# piston_slave.net
KiCad netlist of a schematic drawn in EAGLE
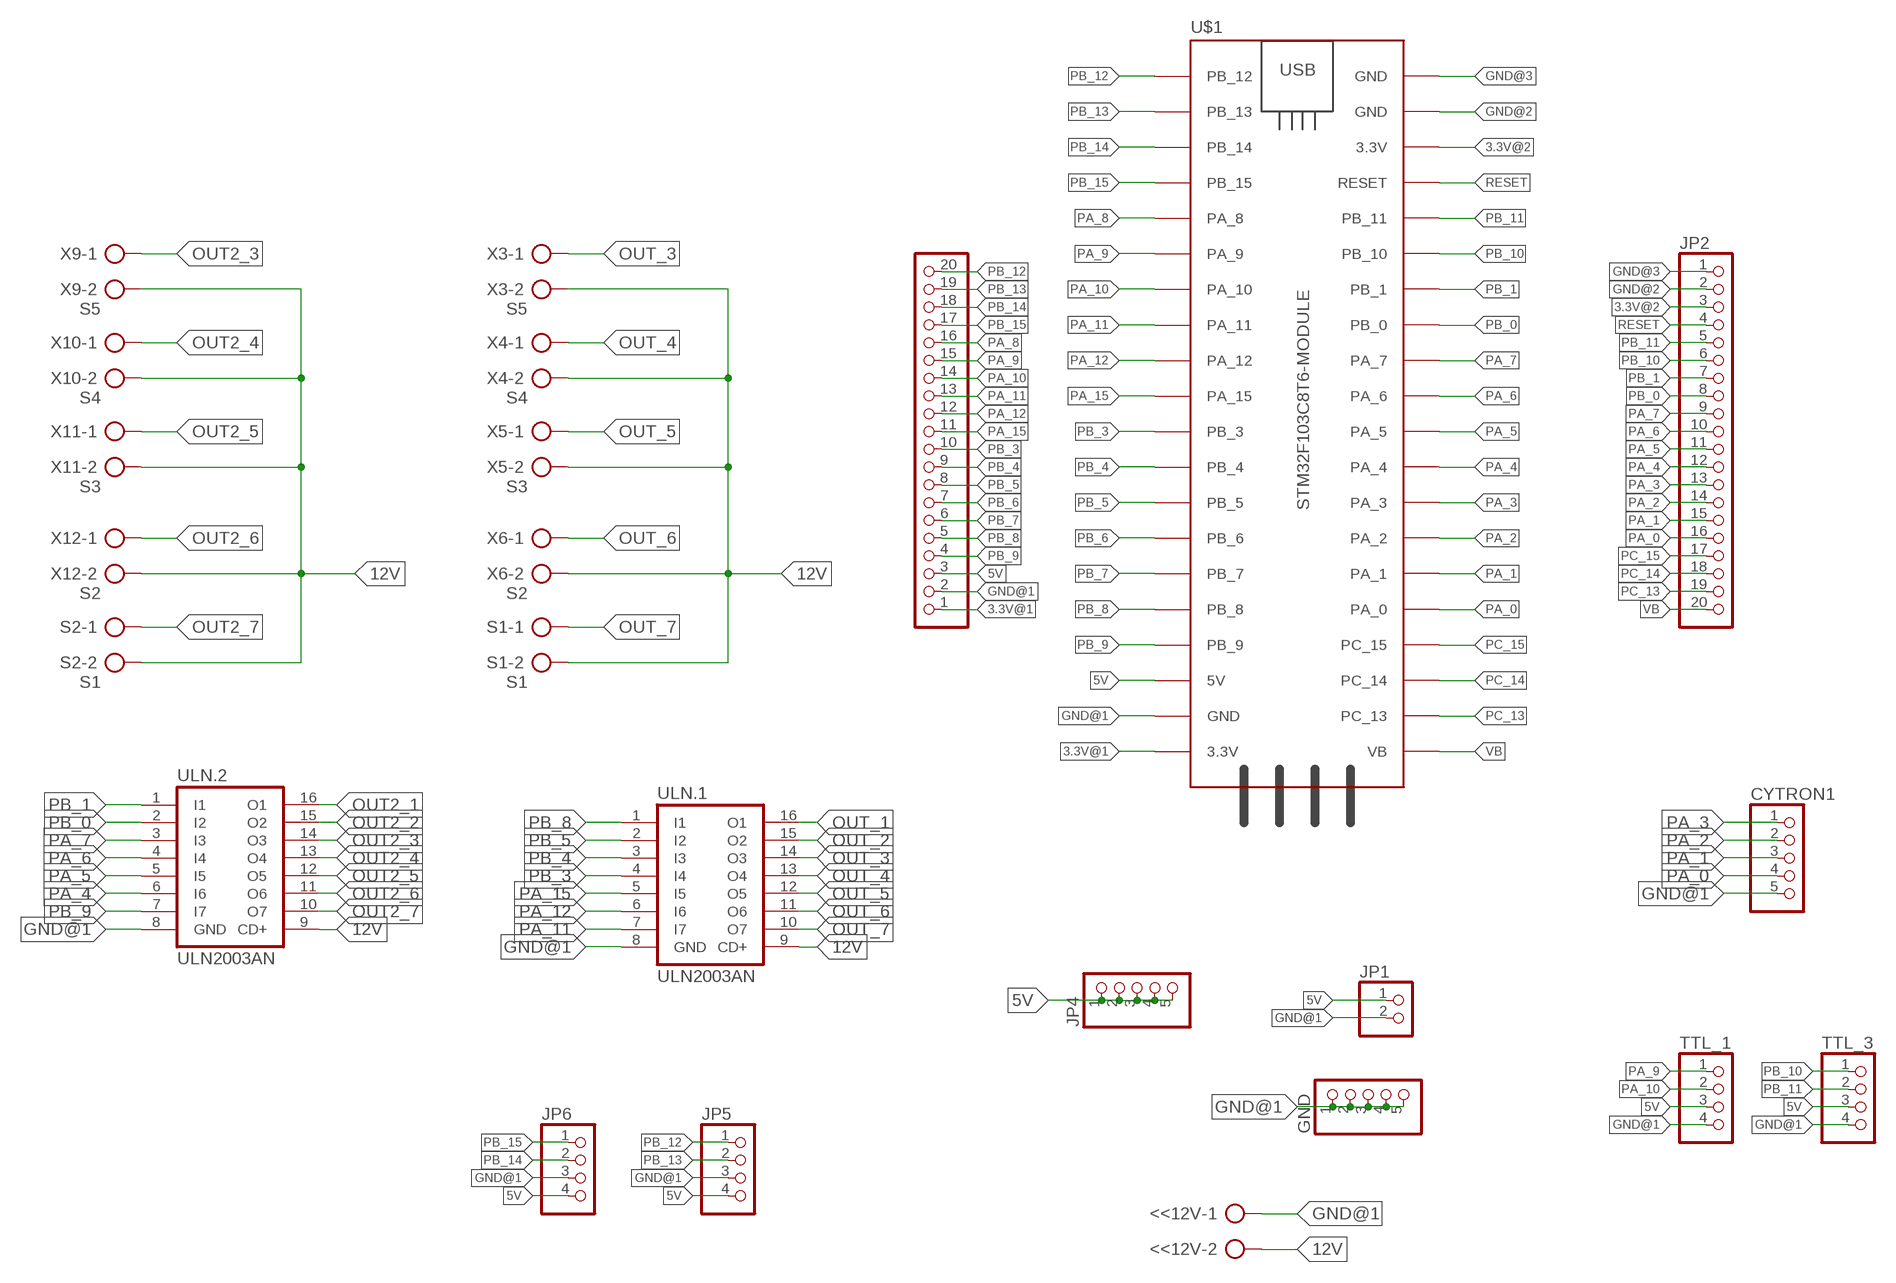
[diagram p0: schematic, sheet 1]

(export (version "E")
  (design (tool "Eeschema 10.0.6"))
  (components
    (comp (ref "<<12V")
      (value "AK300/2")
      (footprint "eagle-import:AK300_2")
      (libsource (lib "eagle-import") (part "AK300/2"))
    )
    (comp (ref "CYTRON1")
      (value "PINHD-5_DATA")
      (footprint "eagle-import:DATA_5")
      (libsource (lib "eagle-import") (part "PINHD-5_DATA"))
    )
    (comp (ref "GND")
      (value "PINHD-1X5")
      (footprint "eagle-import:1X05")
      (libsource (lib "eagle-import") (part "PINHD-1X5"))
    )
    (comp (ref "JP1")
      (value "PINHD-2_DATA")
      (footprint "eagle-import:1X02_DATA")
      (libsource (lib "eagle-import") (part "PINHD-2_DATA"))
    )
    (comp (ref "JP2")
      (value "PINHD-1X20")
      (footprint "eagle-import:1X20")
      (libsource (lib "eagle-import") (part "PINHD-1X20"))
    )
    (comp (ref "JP3")
      (value "PINHD-1X20")
      (footprint "eagle-import:1X20")
      (libsource (lib "eagle-import") (part "PINHD-1X20"))
    )
    (comp (ref "JP4")
      (value "PINHD-1X5")
      (footprint "eagle-import:1X05")
      (libsource (lib "eagle-import") (part "PINHD-1X5"))
    )
    (comp (ref "JP5")
      (value "PINHD-4_DATA")
      (footprint "eagle-import:1X04_DATA")
      (libsource (lib "eagle-import") (part "PINHD-4_DATA"))
    )
    (comp (ref "JP6")
      (value "PINHD-4_DATA")
      (footprint "eagle-import:1X04_DATA")
      (libsource (lib "eagle-import") (part "PINHD-4_DATA"))
    )
    (comp (ref "S1")
      (value "S1")
      (footprint "eagle-import:AK300_2")
      (libsource (lib "eagle-import") (part "AK300/2"))
    )
    (comp (ref "S2")
      (value "S1")
      (footprint "eagle-import:AK300_2")
      (libsource (lib "eagle-import") (part "AK300/2"))
    )
    (comp (ref "TTL_1")
      (value "PINHD-4_DATA")
      (footprint "eagle-import:1X04_DATA")
      (libsource (lib "eagle-import") (part "PINHD-4_DATA"))
    )
    (comp (ref "TTL_3")
      (value "PINHD-4_DATA")
      (footprint "eagle-import:1X04_DATA")
      (libsource (lib "eagle-import") (part "PINHD-4_DATA"))
    )
    (comp (ref "U$1")
      (value "STM32F103C8T6-MODULE")
      (footprint "eagle-import:STM32F103C8T6-MODULE")
      (libsource (lib "eagle-import") (part "STM32F103C8T6-MODULE"))
    )
    (comp (ref "ULN.1")
      (value "ULN2003AN")
      (footprint "eagle-import:DIL16")
      (libsource (lib "eagle-import") (part "ULN2003AN"))
    )
    (comp (ref "ULN.2")
      (value "ULN2003AN")
      (footprint "eagle-import:DIL16")
      (libsource (lib "eagle-import") (part "ULN2003AN"))
    )
    (comp (ref "X3")
      (value "S5")
      (footprint "eagle-import:AK300_2")
      (libsource (lib "eagle-import") (part "AK300/2"))
    )
    (comp (ref "X4")
      (value "S4")
      (footprint "eagle-import:AK300_2")
      (libsource (lib "eagle-import") (part "AK300/2"))
    )
    (comp (ref "X5")
      (value "S3")
      (footprint "eagle-import:AK300_2")
      (libsource (lib "eagle-import") (part "AK300/2"))
    )
    (comp (ref "X6")
      (value "S2")
      (footprint "eagle-import:AK300_2")
      (libsource (lib "eagle-import") (part "AK300/2"))
    )
    (comp (ref "X9")
      (value "S5")
      (footprint "eagle-import:AK300_2")
      (libsource (lib "eagle-import") (part "AK300/2"))
    )
    (comp (ref "X10")
      (value "S4")
      (footprint "eagle-import:AK300_2")
      (libsource (lib "eagle-import") (part "AK300/2"))
    )
    (comp (ref "X11")
      (value "S3")
      (footprint "eagle-import:AK300_2")
      (libsource (lib "eagle-import") (part "AK300/2"))
    )
    (comp (ref "X12")
      (value "S2")
      (footprint "eagle-import:AK300_2")
      (libsource (lib "eagle-import") (part "AK300/2"))
    )
  )
  (nets
    (net (code "1") (name "3.3V@1") (class "Default")
      (node (ref "JP3") (pin "1") (pinfunction "1_1") (pintype "passive"))
      (node (ref "U$1") (pin "3.3V_1") (pinfunction "3.3V_3.3V_1") (pintype "bidirectional"))
    )
    (net (code "2") (name "3.3V@2") (class "Default")
      (node (ref "JP2") (pin "3") (pinfunction "3_3") (pintype "passive"))
      (node (ref "U$1") (pin "3.3V_2") (pinfunction "3.3V_3.3V_2") (pintype "bidirectional"))
    )
    (net (code "3") (name "5V") (class "Default")
      (node (ref "JP1") (pin "1") (pinfunction "1_1") (pintype "passive"))
      (node (ref "JP3") (pin "3") (pinfunction "3_3") (pintype "passive"))
      (node (ref "JP4") (pin "1") (pinfunction "1_1") (pintype "passive"))
      (node (ref "JP4") (pin "2") (pinfunction "2_2") (pintype "passive"))
      (node (ref "JP4") (pin "3") (pinfunction "3_3") (pintype "passive"))
      (node (ref "JP4") (pin "4") (pinfunction "4_4") (pintype "passive"))
      (node (ref "JP4") (pin "5") (pinfunction "5_5") (pintype "passive"))
      (node (ref "JP5") (pin "4") (pinfunction "4_4") (pintype "passive"))
      (node (ref "JP6") (pin "4") (pinfunction "4_4") (pintype "passive"))
      (node (ref "TTL_1") (pin "3") (pinfunction "3_3") (pintype "passive"))
      (node (ref "TTL_3") (pin "3") (pinfunction "3_3") (pintype "passive"))
      (node (ref "U$1") (pin "5V") (pinfunction "5V_5V") (pintype "bidirectional"))
    )
    (net (code "4") (name "12V") (class "Default")
      (node (ref "<<12V") (pin "2") (pinfunction "KL_2") (pintype "passive"))
      (node (ref "S1") (pin "2") (pinfunction "KL_2") (pintype "passive"))
      (node (ref "S2") (pin "2") (pinfunction "KL_2") (pintype "passive"))
      (node (ref "ULN.1") (pin "9") (pinfunction "CD+_9") (pintype "passive"))
      (node (ref "ULN.2") (pin "9") (pinfunction "CD+_9") (pintype "passive"))
      (node (ref "X10") (pin "2") (pinfunction "KL_2") (pintype "passive"))
      (node (ref "X11") (pin "2") (pinfunction "KL_2") (pintype "passive"))
      (node (ref "X12") (pin "2") (pinfunction "KL_2") (pintype "passive"))
      (node (ref "X3") (pin "2") (pinfunction "KL_2") (pintype "passive"))
      (node (ref "X4") (pin "2") (pinfunction "KL_2") (pintype "passive"))
      (node (ref "X5") (pin "2") (pinfunction "KL_2") (pintype "passive"))
      (node (ref "X6") (pin "2") (pinfunction "KL_2") (pintype "passive"))
      (node (ref "X9") (pin "2") (pinfunction "KL_2") (pintype "passive"))
    )
    (net (code "5") (name "GND@1") (class "Default")
      (node (ref "<<12V") (pin "1") (pinfunction "KL_1") (pintype "passive"))
      (node (ref "CYTRON1") (pin "5") (pinfunction "5_5") (pintype "passive"))
      (node (ref "GND") (pin "1") (pinfunction "1_1") (pintype "passive"))
      (node (ref "GND") (pin "2") (pinfunction "2_2") (pintype "passive"))
      (node (ref "GND") (pin "3") (pinfunction "3_3") (pintype "passive"))
      (node (ref "GND") (pin "4") (pinfunction "4_4") (pintype "passive"))
      (node (ref "GND") (pin "5") (pinfunction "5_5") (pintype "passive"))
      (node (ref "JP1") (pin "2") (pinfunction "2_2") (pintype "passive"))
      (node (ref "JP3") (pin "2") (pinfunction "2_2") (pintype "passive"))
      (node (ref "JP5") (pin "3") (pinfunction "3_3") (pintype "passive"))
      (node (ref "JP6") (pin "3") (pinfunction "3_3") (pintype "passive"))
      (node (ref "TTL_1") (pin "4") (pinfunction "4_4") (pintype "passive"))
      (node (ref "TTL_3") (pin "4") (pinfunction "4_4") (pintype "passive"))
      (node (ref "U$1") (pin "GND_1") (pinfunction "GND_GND_1") (pintype "bidirectional"))
      (node (ref "ULN.1") (pin "8") (pinfunction "GND_8") (pintype "power_in"))
      (node (ref "ULN.2") (pin "8") (pinfunction "GND_8") (pintype "power_in"))
    )
    (net (code "6") (name "GND@2") (class "Default")
      (node (ref "JP2") (pin "2") (pinfunction "2_2") (pintype "passive"))
      (node (ref "U$1") (pin "GND_2") (pinfunction "GND_GND_2") (pintype "bidirectional"))
    )
    (net (code "7") (name "GND@3") (class "Default")
      (node (ref "JP2") (pin "1") (pinfunction "1_1") (pintype "passive"))
      (node (ref "U$1") (pin "GND_3") (pinfunction "GND_GND_3") (pintype "power_in"))
    )
    (net (code "8") (name "OUT2_1") (class "Default")
      (node (ref "ULN.2") (pin "16") (pinfunction "O1_16") (pintype "open_collector"))
    )
    (net (code "9") (name "OUT2_2") (class "Default")
      (node (ref "ULN.2") (pin "15") (pinfunction "O2_15") (pintype "open_collector"))
    )
    (net (code "10") (name "OUT2_3") (class "Default")
      (node (ref "ULN.2") (pin "14") (pinfunction "O3_14") (pintype "open_collector"))
      (node (ref "X9") (pin "1") (pinfunction "KL_1") (pintype "passive"))
    )
    (net (code "11") (name "OUT2_4") (class "Default")
      (node (ref "ULN.2") (pin "13") (pinfunction "O4_13") (pintype "open_collector"))
      (node (ref "X10") (pin "1") (pinfunction "KL_1") (pintype "passive"))
    )
    (net (code "12") (name "OUT2_5") (class "Default")
      (node (ref "ULN.2") (pin "12") (pinfunction "O5_12") (pintype "open_collector"))
      (node (ref "X11") (pin "1") (pinfunction "KL_1") (pintype "passive"))
    )
    (net (code "13") (name "OUT2_6") (class "Default")
      (node (ref "ULN.2") (pin "11") (pinfunction "O6_11") (pintype "open_collector"))
      (node (ref "X12") (pin "1") (pinfunction "KL_1") (pintype "passive"))
    )
    (net (code "14") (name "OUT2_7") (class "Default")
      (node (ref "S2") (pin "1") (pinfunction "KL_1") (pintype "passive"))
      (node (ref "ULN.2") (pin "10") (pinfunction "O7_10") (pintype "open_collector"))
    )
    (net (code "15") (name "OUT_1") (class "Default")
      (node (ref "ULN.1") (pin "16") (pinfunction "O1_16") (pintype "open_collector"))
    )
    (net (code "16") (name "OUT_2") (class "Default")
      (node (ref "ULN.1") (pin "15") (pinfunction "O2_15") (pintype "open_collector"))
    )
    (net (code "17") (name "OUT_3") (class "Default")
      (node (ref "ULN.1") (pin "14") (pinfunction "O3_14") (pintype "open_collector"))
      (node (ref "X3") (pin "1") (pinfunction "KL_1") (pintype "passive"))
    )
    (net (code "18") (name "OUT_4") (class "Default")
      (node (ref "ULN.1") (pin "13") (pinfunction "O4_13") (pintype "open_collector"))
      (node (ref "X4") (pin "1") (pinfunction "KL_1") (pintype "passive"))
    )
    (net (code "19") (name "OUT_5") (class "Default")
      (node (ref "ULN.1") (pin "12") (pinfunction "O5_12") (pintype "open_collector"))
      (node (ref "X5") (pin "1") (pinfunction "KL_1") (pintype "passive"))
    )
    (net (code "20") (name "OUT_6") (class "Default")
      (node (ref "ULN.1") (pin "11") (pinfunction "O6_11") (pintype "open_collector"))
      (node (ref "X6") (pin "1") (pinfunction "KL_1") (pintype "passive"))
    )
    (net (code "21") (name "OUT_7") (class "Default")
      (node (ref "S1") (pin "1") (pinfunction "KL_1") (pintype "passive"))
      (node (ref "ULN.1") (pin "10") (pinfunction "O7_10") (pintype "open_collector"))
    )
    (net (code "22") (name "PA_0") (class "Default")
      (node (ref "CYTRON1") (pin "4") (pinfunction "4_4") (pintype "passive"))
      (node (ref "JP2") (pin "16") (pinfunction "16_16") (pintype "passive"))
      (node (ref "U$1") (pin "PA_0") (pinfunction "PA_0_PA_0") (pintype "bidirectional"))
    )
    (net (code "23") (name "PA_1") (class "Default")
      (node (ref "CYTRON1") (pin "3") (pinfunction "3_3") (pintype "passive"))
      (node (ref "JP2") (pin "15") (pinfunction "15_15") (pintype "passive"))
      (node (ref "U$1") (pin "PA_1") (pinfunction "PA_1_PA_1") (pintype "bidirectional"))
    )
    (net (code "24") (name "PA_2") (class "Default")
      (node (ref "CYTRON1") (pin "2") (pinfunction "2_2") (pintype "passive"))
      (node (ref "JP2") (pin "14") (pinfunction "14_14") (pintype "passive"))
      (node (ref "U$1") (pin "PA_2") (pinfunction "PA_2_PA_2") (pintype "bidirectional"))
    )
    (net (code "25") (name "PA_3") (class "Default")
      (node (ref "CYTRON1") (pin "1") (pinfunction "1_1") (pintype "passive"))
      (node (ref "JP2") (pin "13") (pinfunction "13_13") (pintype "passive"))
      (node (ref "U$1") (pin "PA_3") (pinfunction "PA_3_PA_3") (pintype "bidirectional"))
    )
    (net (code "26") (name "PA_4") (class "Default")
      (node (ref "JP2") (pin "12") (pinfunction "12_12") (pintype "passive"))
      (node (ref "U$1") (pin "PA_4") (pinfunction "PA_4_PA_4") (pintype "bidirectional"))
      (node (ref "ULN.2") (pin "6") (pinfunction "I6_6") (pintype "input"))
    )
    (net (code "27") (name "PA_5") (class "Default")
      (node (ref "JP2") (pin "11") (pinfunction "11_11") (pintype "passive"))
      (node (ref "U$1") (pin "PA_5") (pinfunction "PA_5_PA_5") (pintype "bidirectional"))
      (node (ref "ULN.2") (pin "5") (pinfunction "I5_5") (pintype "input"))
    )
    (net (code "28") (name "PA_6") (class "Default")
      (node (ref "JP2") (pin "10") (pinfunction "10_10") (pintype "passive"))
      (node (ref "U$1") (pin "PA_6") (pinfunction "PA_6_PA_6") (pintype "bidirectional"))
      (node (ref "ULN.2") (pin "4") (pinfunction "I4_4") (pintype "input"))
    )
    (net (code "29") (name "PA_7") (class "Default")
      (node (ref "JP2") (pin "9") (pinfunction "9_9") (pintype "passive"))
      (node (ref "U$1") (pin "PA_7") (pinfunction "PA_7_PA_7") (pintype "bidirectional"))
      (node (ref "ULN.2") (pin "3") (pinfunction "I3_3") (pintype "input"))
    )
    (net (code "30") (name "PA_8") (class "Default")
      (node (ref "JP3") (pin "16") (pinfunction "16_16") (pintype "passive"))
      (node (ref "U$1") (pin "PA_8") (pinfunction "PA_8_PA_8") (pintype "bidirectional"))
    )
    (net (code "31") (name "PA_9") (class "Default")
      (node (ref "JP3") (pin "15") (pinfunction "15_15") (pintype "passive"))
      (node (ref "TTL_1") (pin "1") (pinfunction "1_1") (pintype "passive"))
      (node (ref "U$1") (pin "PA_9") (pinfunction "PA_9_PA_9") (pintype "bidirectional"))
    )
    (net (code "32") (name "PA_10") (class "Default")
      (node (ref "JP3") (pin "14") (pinfunction "14_14") (pintype "passive"))
      (node (ref "TTL_1") (pin "2") (pinfunction "2_2") (pintype "passive"))
      (node (ref "U$1") (pin "PA_10") (pinfunction "PA_10_PA_10") (pintype "bidirectional"))
    )
    (net (code "33") (name "PA_11") (class "Default")
      (node (ref "JP3") (pin "13") (pinfunction "13_13") (pintype "passive"))
      (node (ref "U$1") (pin "PA_11") (pinfunction "PA_11_PA_11") (pintype "bidirectional"))
      (node (ref "ULN.1") (pin "7") (pinfunction "I7_7") (pintype "input"))
    )
    (net (code "34") (name "PA_12") (class "Default")
      (node (ref "JP3") (pin "12") (pinfunction "12_12") (pintype "passive"))
      (node (ref "U$1") (pin "PA_12") (pinfunction "PA_12_PA_12") (pintype "bidirectional"))
      (node (ref "ULN.1") (pin "6") (pinfunction "I6_6") (pintype "input"))
    )
    (net (code "35") (name "PA_15") (class "Default")
      (node (ref "JP3") (pin "11") (pinfunction "11_11") (pintype "passive"))
      (node (ref "U$1") (pin "PA_15") (pinfunction "PA_15_PA_15") (pintype "bidirectional"))
      (node (ref "ULN.1") (pin "5") (pinfunction "I5_5") (pintype "input"))
    )
    (net (code "36") (name "PB_0") (class "Default")
      (node (ref "JP2") (pin "8") (pinfunction "8_8") (pintype "passive"))
      (node (ref "U$1") (pin "PB_0") (pinfunction "PB_0_PB_0") (pintype "bidirectional"))
      (node (ref "ULN.2") (pin "2") (pinfunction "I2_2") (pintype "input"))
    )
    (net (code "37") (name "PB_1") (class "Default")
      (node (ref "JP2") (pin "7") (pinfunction "7_7") (pintype "passive"))
      (node (ref "U$1") (pin "PB_1") (pinfunction "PB_1_PB_1") (pintype "bidirectional"))
      (node (ref "ULN.2") (pin "1") (pinfunction "I1_1") (pintype "input"))
    )
    (net (code "38") (name "PB_3") (class "Default")
      (node (ref "JP3") (pin "10") (pinfunction "10_10") (pintype "passive"))
      (node (ref "U$1") (pin "PB_3") (pinfunction "PB_3_PB_3") (pintype "bidirectional"))
      (node (ref "ULN.1") (pin "4") (pinfunction "I4_4") (pintype "input"))
    )
    (net (code "39") (name "PB_4") (class "Default")
      (node (ref "JP3") (pin "9") (pinfunction "9_9") (pintype "passive"))
      (node (ref "U$1") (pin "PB_4") (pinfunction "PB_4_PB_4") (pintype "bidirectional"))
      (node (ref "ULN.1") (pin "3") (pinfunction "I3_3") (pintype "input"))
    )
    (net (code "40") (name "PB_5") (class "Default")
      (node (ref "JP3") (pin "8") (pinfunction "8_8") (pintype "passive"))
      (node (ref "U$1") (pin "PB_5") (pinfunction "PB_5_PB_5") (pintype "bidirectional"))
      (node (ref "ULN.1") (pin "2") (pinfunction "I2_2") (pintype "input"))
    )
    (net (code "41") (name "PB_6") (class "Default")
      (node (ref "JP3") (pin "7") (pinfunction "7_7") (pintype "passive"))
      (node (ref "U$1") (pin "PB_6") (pinfunction "PB_6_PB_6") (pintype "bidirectional"))
    )
    (net (code "42") (name "PB_7") (class "Default")
      (node (ref "JP3") (pin "6") (pinfunction "6_6") (pintype "passive"))
      (node (ref "U$1") (pin "PB_7") (pinfunction "PB_7_PB_7") (pintype "bidirectional"))
    )
    (net (code "43") (name "PB_8") (class "Default")
      (node (ref "JP3") (pin "5") (pinfunction "5_5") (pintype "passive"))
      (node (ref "U$1") (pin "PB_8") (pinfunction "PB_8_PB_8") (pintype "bidirectional"))
      (node (ref "ULN.1") (pin "1") (pinfunction "I1_1") (pintype "input"))
    )
    (net (code "44") (name "PB_9") (class "Default")
      (node (ref "JP3") (pin "4") (pinfunction "4_4") (pintype "passive"))
      (node (ref "U$1") (pin "PB_9") (pinfunction "PB_9_PB_9") (pintype "bidirectional"))
      (node (ref "ULN.2") (pin "7") (pinfunction "I7_7") (pintype "input"))
    )
    (net (code "45") (name "PB_10") (class "Default")
      (node (ref "JP2") (pin "6") (pinfunction "6_6") (pintype "passive"))
      (node (ref "TTL_3") (pin "1") (pinfunction "1_1") (pintype "passive"))
      (node (ref "U$1") (pin "PB_10") (pinfunction "PB_10_PB_10") (pintype "bidirectional"))
    )
    (net (code "46") (name "PB_11") (class "Default")
      (node (ref "JP2") (pin "5") (pinfunction "5_5") (pintype "passive"))
      (node (ref "TTL_3") (pin "2") (pinfunction "2_2") (pintype "passive"))
      (node (ref "U$1") (pin "PB_11") (pinfunction "PB_11_PB_11") (pintype "bidirectional"))
    )
    (net (code "47") (name "PB_12") (class "Default")
      (node (ref "JP3") (pin "20") (pinfunction "20_20") (pintype "passive"))
      (node (ref "JP5") (pin "1") (pinfunction "1_1") (pintype "passive"))
      (node (ref "U$1") (pin "PB_12") (pinfunction "PB_12_PB_12") (pintype "bidirectional"))
    )
    (net (code "48") (name "PB_13") (class "Default")
      (node (ref "JP3") (pin "19") (pinfunction "19_19") (pintype "passive"))
      (node (ref "JP5") (pin "2") (pinfunction "2_2") (pintype "passive"))
      (node (ref "U$1") (pin "PB_13") (pinfunction "PB_13_PB_13") (pintype "bidirectional"))
    )
    (net (code "49") (name "PB_14") (class "Default")
      (node (ref "JP3") (pin "18") (pinfunction "18_18") (pintype "passive"))
      (node (ref "JP6") (pin "2") (pinfunction "2_2") (pintype "passive"))
      (node (ref "U$1") (pin "PB_14") (pinfunction "PB_14_PB_14") (pintype "bidirectional"))
    )
    (net (code "50") (name "PB_15") (class "Default")
      (node (ref "JP3") (pin "17") (pinfunction "17_17") (pintype "passive"))
      (node (ref "JP6") (pin "1") (pinfunction "1_1") (pintype "passive"))
      (node (ref "U$1") (pin "PB_15") (pinfunction "PB_15_PB_15") (pintype "bidirectional"))
    )
    (net (code "51") (name "PC_13") (class "Default")
      (node (ref "JP2") (pin "19") (pinfunction "19_19") (pintype "passive"))
      (node (ref "U$1") (pin "PC_13") (pinfunction "PC_13_PC_13") (pintype "bidirectional"))
    )
    (net (code "52") (name "PC_14") (class "Default")
      (node (ref "JP2") (pin "18") (pinfunction "18_18") (pintype "passive"))
      (node (ref "U$1") (pin "PC_14") (pinfunction "PC_14_PC_14") (pintype "bidirectional"))
    )
    (net (code "53") (name "PC_15") (class "Default")
      (node (ref "JP2") (pin "17") (pinfunction "17_17") (pintype "passive"))
      (node (ref "U$1") (pin "PC_15") (pinfunction "PC_15_PC_15") (pintype "bidirectional"))
    )
    (net (code "54") (name "RESET") (class "Default")
      (node (ref "JP2") (pin "4") (pinfunction "4_4") (pintype "passive"))
      (node (ref "U$1") (pin "RESET") (pinfunction "RESET_RESET") (pintype "bidirectional"))
    )
    (net (code "55") (name "VB") (class "Default")
      (node (ref "JP2") (pin "20") (pinfunction "20_20") (pintype "passive"))
      (node (ref "U$1") (pin "VB") (pinfunction "VB_VB") (pintype "bidirectional"))
    )
  )
)
